# microcontroller.net
KiCad netlist of a schematic drawn in EAGLE
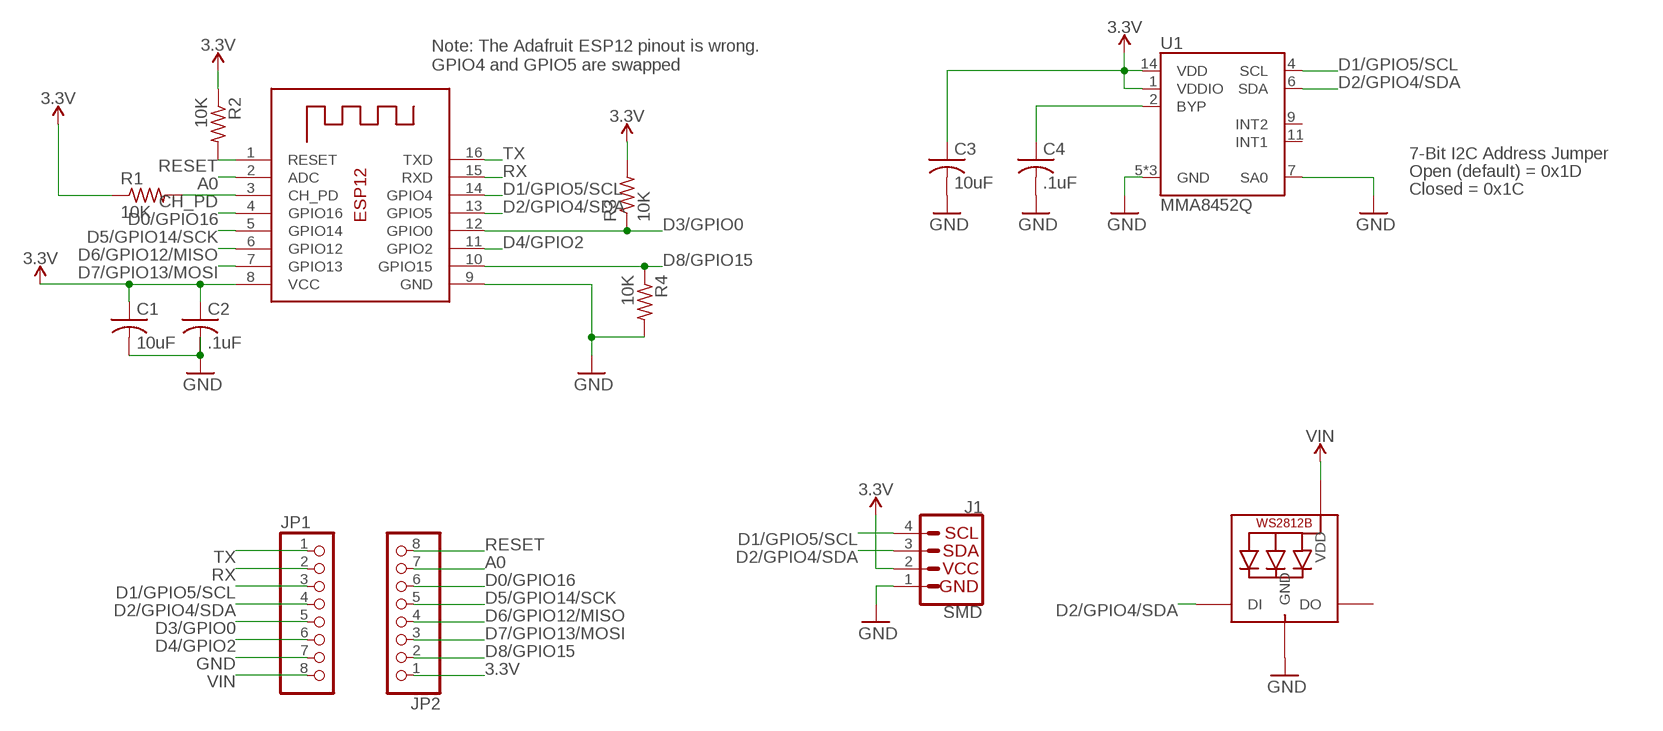
[diagram p0: schematic, sheet 1]

(export (version "E")
  (design (tool "Eeschema 10.0.6"))
  (components
    (comp (ref "C1")
      (value "10uF")
      (footprint "eagle-import:C0805")
      (fields (field (name "MPN") "LMK212BJ106KG-T"))
      (libsource (lib "eagle-import") (part "C-USC0805"))
    )
    (comp (ref "C2")
      (value ".1uF")
      (footprint "eagle-import:C0805")
      (fields (field (name "MPN") "C0805C104M3RACTU"))
      (libsource (lib "eagle-import") (part "C-USC0805"))
    )
    (comp (ref "C3")
      (value "10uF")
      (footprint "eagle-import:C0805")
      (fields (field (name "MPN") "LMK212BJ106KG-T"))
      (libsource (lib "eagle-import") (part "C-USC0805"))
    )
    (comp (ref "C4")
      (value ".1uF")
      (footprint "eagle-import:C0805")
      (fields (field (name "MPN") "C0805C104M3RACTU"))
      (libsource (lib "eagle-import") (part "C-USC0805"))
    )
    (comp (ref "J1")
      (value "SMD")
      (footprint "eagle-import:1X04_1MM_RA")
      (fields (field (name "MPN") "PRT-14417"))
      (libsource (lib "eagle-import") (part "I2C_STANDARDJS-1MM"))
    )
    (comp (ref "JP1")
      (value "PINHD-1X8CLEANBIG")
      (footprint "eagle-import:1X08-CLEANBIG")
      (fields (field (name "MPN") "83-15410"))
      (libsource (lib "eagle-import") (part "PINHD-1X8CLEANBIG"))
    )
    (comp (ref "JP2")
      (value "PINHD-1X8CLEANBIG")
      (footprint "eagle-import:1X08-CLEANBIG")
      (fields (field (name "MPN") "83-15410"))
      (libsource (lib "eagle-import") (part "PINHD-1X8CLEANBIG"))
    )
    (comp (ref "LED1")
      (value "WS2812B5050")
      (footprint "eagle-import:WS2812B")
      (fields (field (name "MPN") "1655"))
      (libsource (lib "eagle-import") (part "WS2812B5050"))
    )
    (comp (ref "R1")
      (value "10K")
      (footprint "eagle-import:R0805")
      (fields (field (name "MPN") "CRCW080510K0FKEAC"))
      (libsource (lib "eagle-import") (part "R-US_R0805"))
    )
    (comp (ref "R2")
      (value "10K")
      (footprint "eagle-import:R0805")
      (fields (field (name "MPN") "CRCW080510K0FKEAC"))
      (libsource (lib "eagle-import") (part "R-US_R0805"))
    )
    (comp (ref "R3")
      (value "10K")
      (footprint "eagle-import:R0805")
      (fields (field (name "MPN") "CRCW080510K0FKEAC"))
      (libsource (lib "eagle-import") (part "R-US_R0805"))
    )
    (comp (ref "R4")
      (value "10K")
      (footprint "eagle-import:R0805")
      (fields (field (name "MPN") "CRCW080510K0FKEAC"))
      (libsource (lib "eagle-import") (part "R-US_R0805"))
    )
    (comp (ref "U1")
      (value "MMA8452Q")
      (footprint "eagle-import:QFN-16_0.5MM")
      (fields (field (name "MPN") "MMA8452QR1"))
      (libsource (lib "eagle-import") (part "MMA8452Q"))
    )
    (comp (ref "X1")
      (value "ESP-12")
      (footprint "eagle-import:ESP-12")
      (fields (field (name "MPN") "ESP-12F(ESP8266MOD)"))
      (libsource (lib "eagle-import") (part "ESP-12"))
    )
  )
  (nets
    (net (code "1") (name "/A0") (class "Default")
      (node (ref "JP2") (pin "7") (pinfunction "7_7") (pintype "passive"))
      (node (ref "X1") (pin "2") (pinfunction "ADC_2") (pintype "passive"))
    )
    (net (code "2") (name "/CH_PD") (class "Default")
      (node (ref "R1") (pin "2") (pinfunction "2_2") (pintype "passive"))
      (node (ref "X1") (pin "3") (pinfunction "CH_PD_3") (pintype "input"))
    )
    (net (code "3") (name "/D0{slash}GPIO16") (class "Default")
      (node (ref "JP2") (pin "6") (pinfunction "6_6") (pintype "passive"))
      (node (ref "X1") (pin "4") (pinfunction "GPIO16_4") (pintype "bidirectional"))
    )
    (net (code "4") (name "/D1{slash}GPIO5{slash}SCL") (class "Default")
      (node (ref "J1") (pin "4") (pinfunction "SCL_4") (pintype "passive"))
      (node (ref "JP1") (pin "3") (pinfunction "3_3") (pintype "passive"))
      (node (ref "U1") (pin "4") (pinfunction "SCL_4") (pintype "bidirectional"))
      (node (ref "X1") (pin "14") (pinfunction "GPIO4_14") (pintype "bidirectional"))
    )
    (net (code "5") (name "/D2{slash}GPIO4{slash}SDA") (class "Default")
      (node (ref "J1") (pin "3") (pinfunction "SDA_3") (pintype "passive"))
      (node (ref "JP1") (pin "4") (pinfunction "4_4") (pintype "passive"))
      (node (ref "LED1") (pin "4-DIN") (pinfunction "DI_4-DIN") (pintype "input"))
      (node (ref "U1") (pin "6") (pinfunction "SDA_6") (pintype "bidirectional"))
      (node (ref "X1") (pin "13") (pinfunction "GPIO5_13") (pintype "bidirectional"))
    )
    (net (code "6") (name "/D3{slash}GPIO0") (class "Default")
      (node (ref "JP1") (pin "5") (pinfunction "5_5") (pintype "passive"))
      (node (ref "R3") (pin "1") (pinfunction "1_1") (pintype "passive"))
      (node (ref "X1") (pin "12") (pinfunction "GPIO0_12") (pintype "bidirectional"))
    )
    (net (code "7") (name "/D4{slash}GPIO2") (class "Default")
      (node (ref "JP1") (pin "6") (pinfunction "6_6") (pintype "passive"))
      (node (ref "X1") (pin "11") (pinfunction "GPIO2_11") (pintype "bidirectional"))
    )
    (net (code "8") (name "/D5{slash}GPIO14{slash}SCK") (class "Default")
      (node (ref "JP2") (pin "5") (pinfunction "5_5") (pintype "passive"))
      (node (ref "X1") (pin "5") (pinfunction "GPIO14_5") (pintype "bidirectional"))
    )
    (net (code "9") (name "/D6{slash}GPIO12{slash}MISO") (class "Default")
      (node (ref "JP2") (pin "4") (pinfunction "4_4") (pintype "passive"))
      (node (ref "X1") (pin "6") (pinfunction "GPIO12_6") (pintype "bidirectional"))
    )
    (net (code "10") (name "/D7{slash}GPIO13{slash}MOSI") (class "Default")
      (node (ref "JP2") (pin "3") (pinfunction "3_3") (pintype "passive"))
      (node (ref "X1") (pin "7") (pinfunction "GPIO13_7") (pintype "bidirectional"))
    )
    (net (code "11") (name "/D8{slash}GPIO15") (class "Default")
      (node (ref "JP2") (pin "2") (pinfunction "2_2") (pintype "passive"))
      (node (ref "R4") (pin "1") (pinfunction "1_1") (pintype "passive"))
      (node (ref "X1") (pin "10") (pinfunction "GPIO15_10") (pintype "bidirectional"))
    )
    (net (code "12") (name "/RESET") (class "Default")
      (node (ref "JP2") (pin "8") (pinfunction "8_8") (pintype "passive"))
      (node (ref "R2") (pin "2") (pinfunction "2_2") (pintype "passive"))
      (node (ref "X1") (pin "1") (pinfunction "RESET_1") (pintype "input"))
    )
    (net (code "13") (name "/RX") (class "Default")
      (node (ref "JP1") (pin "2") (pinfunction "2_2") (pintype "passive"))
      (node (ref "X1") (pin "15") (pinfunction "RXD_15") (pintype "input"))
    )
    (net (code "14") (name "/TX") (class "Default")
      (node (ref "JP1") (pin "1") (pinfunction "1_1") (pintype "passive"))
      (node (ref "X1") (pin "16") (pinfunction "TXD_16") (pintype "output"))
    )
    (net (code "15") (name "3.3V") (class "Default")
      (node (ref "C1") (pin "1") (pinfunction "1_1") (pintype "passive"))
      (node (ref "C2") (pin "1") (pinfunction "1_1") (pintype "passive"))
      (node (ref "C3") (pin "1") (pinfunction "1_1") (pintype "passive"))
      (node (ref "J1") (pin "2") (pinfunction "VCC_2") (pintype "power_in"))
      (node (ref "JP2") (pin "1") (pinfunction "1_1") (pintype "passive"))
      (node (ref "R1") (pin "1") (pinfunction "1_1") (pintype "passive"))
      (node (ref "R2") (pin "1") (pinfunction "1_1") (pintype "passive"))
      (node (ref "R3") (pin "2") (pinfunction "2_2") (pintype "passive"))
      (node (ref "U1") (pin "1") (pinfunction "VDDIO_1") (pintype "bidirectional"))
      (node (ref "U1") (pin "14") (pinfunction "VDD_14") (pintype "bidirectional"))
      (node (ref "X1") (pin "8") (pinfunction "VCC_8") (pintype "power_in"))
    )
    (net (code "16") (name "GND") (class "Default")
      (node (ref "C1") (pin "2") (pinfunction "2_2") (pintype "passive"))
      (node (ref "C2") (pin "2") (pinfunction "2_2") (pintype "passive"))
      (node (ref "C3") (pin "2") (pinfunction "2_2") (pintype "passive"))
      (node (ref "C4") (pin "2") (pinfunction "2_2") (pintype "passive"))
      (node (ref "J1") (pin "1") (pinfunction "GND_1") (pintype "power_in"))
      (node (ref "JP1") (pin "7") (pinfunction "7_7") (pintype "passive"))
      (node (ref "LED1") (pin "3-GND") (pinfunction "GND_3-GND") (pintype "power_in"))
      (node (ref "R4") (pin "2") (pinfunction "2_2") (pintype "passive"))
      (node (ref "U1") (pin "10") (pinfunction "GND_10") (pintype "bidirectional"))
      (node (ref "U1") (pin "12") (pinfunction "GND_12") (pintype "bidirectional"))
      (node (ref "U1") (pin "5") (pinfunction "GND_5") (pintype "bidirectional"))
      (node (ref "U1") (pin "7") (pinfunction "SA0_7") (pintype "bidirectional"))
      (node (ref "X1") (pin "9") (pinfunction "GND_9") (pintype "power_in"))
    )
    (net (code "17") (name "Net-(U1-BYP)") (class "Default")
      (node (ref "C4") (pin "1") (pinfunction "1_1") (pintype "passive"))
      (node (ref "U1") (pin "2") (pinfunction "BYP_2") (pintype "bidirectional"))
    )
    (net (code "18") (name "VIN") (class "Default")
      (node (ref "JP1") (pin "8") (pinfunction "8_8") (pintype "passive"))
      (node (ref "LED1") (pin "1-VDD") (pinfunction "VDD_1-VDD") (pintype "power_in"))
    )
    (net (code "19") (name "unconnected-(LED1-DO-Pad2-DOUT)") (class "Default")
      (node (ref "LED1") (pin "2-DOUT") (pinfunction "DO_2-DOUT") (pintype "output"))
    )
    (net (code "20") (name "unconnected-(U1-INT1-Pad11)") (class "Default")
      (node (ref "U1") (pin "11") (pinfunction "INT1_11") (pintype "bidirectional"))
    )
    (net (code "21") (name "unconnected-(U1-INT2-Pad9)") (class "Default")
      (node (ref "U1") (pin "9") (pinfunction "INT2_9") (pintype "bidirectional"))
    )
  )
)
